# STM32_Power.net
KiCad netlist of a schematic drawn in Altium Designer
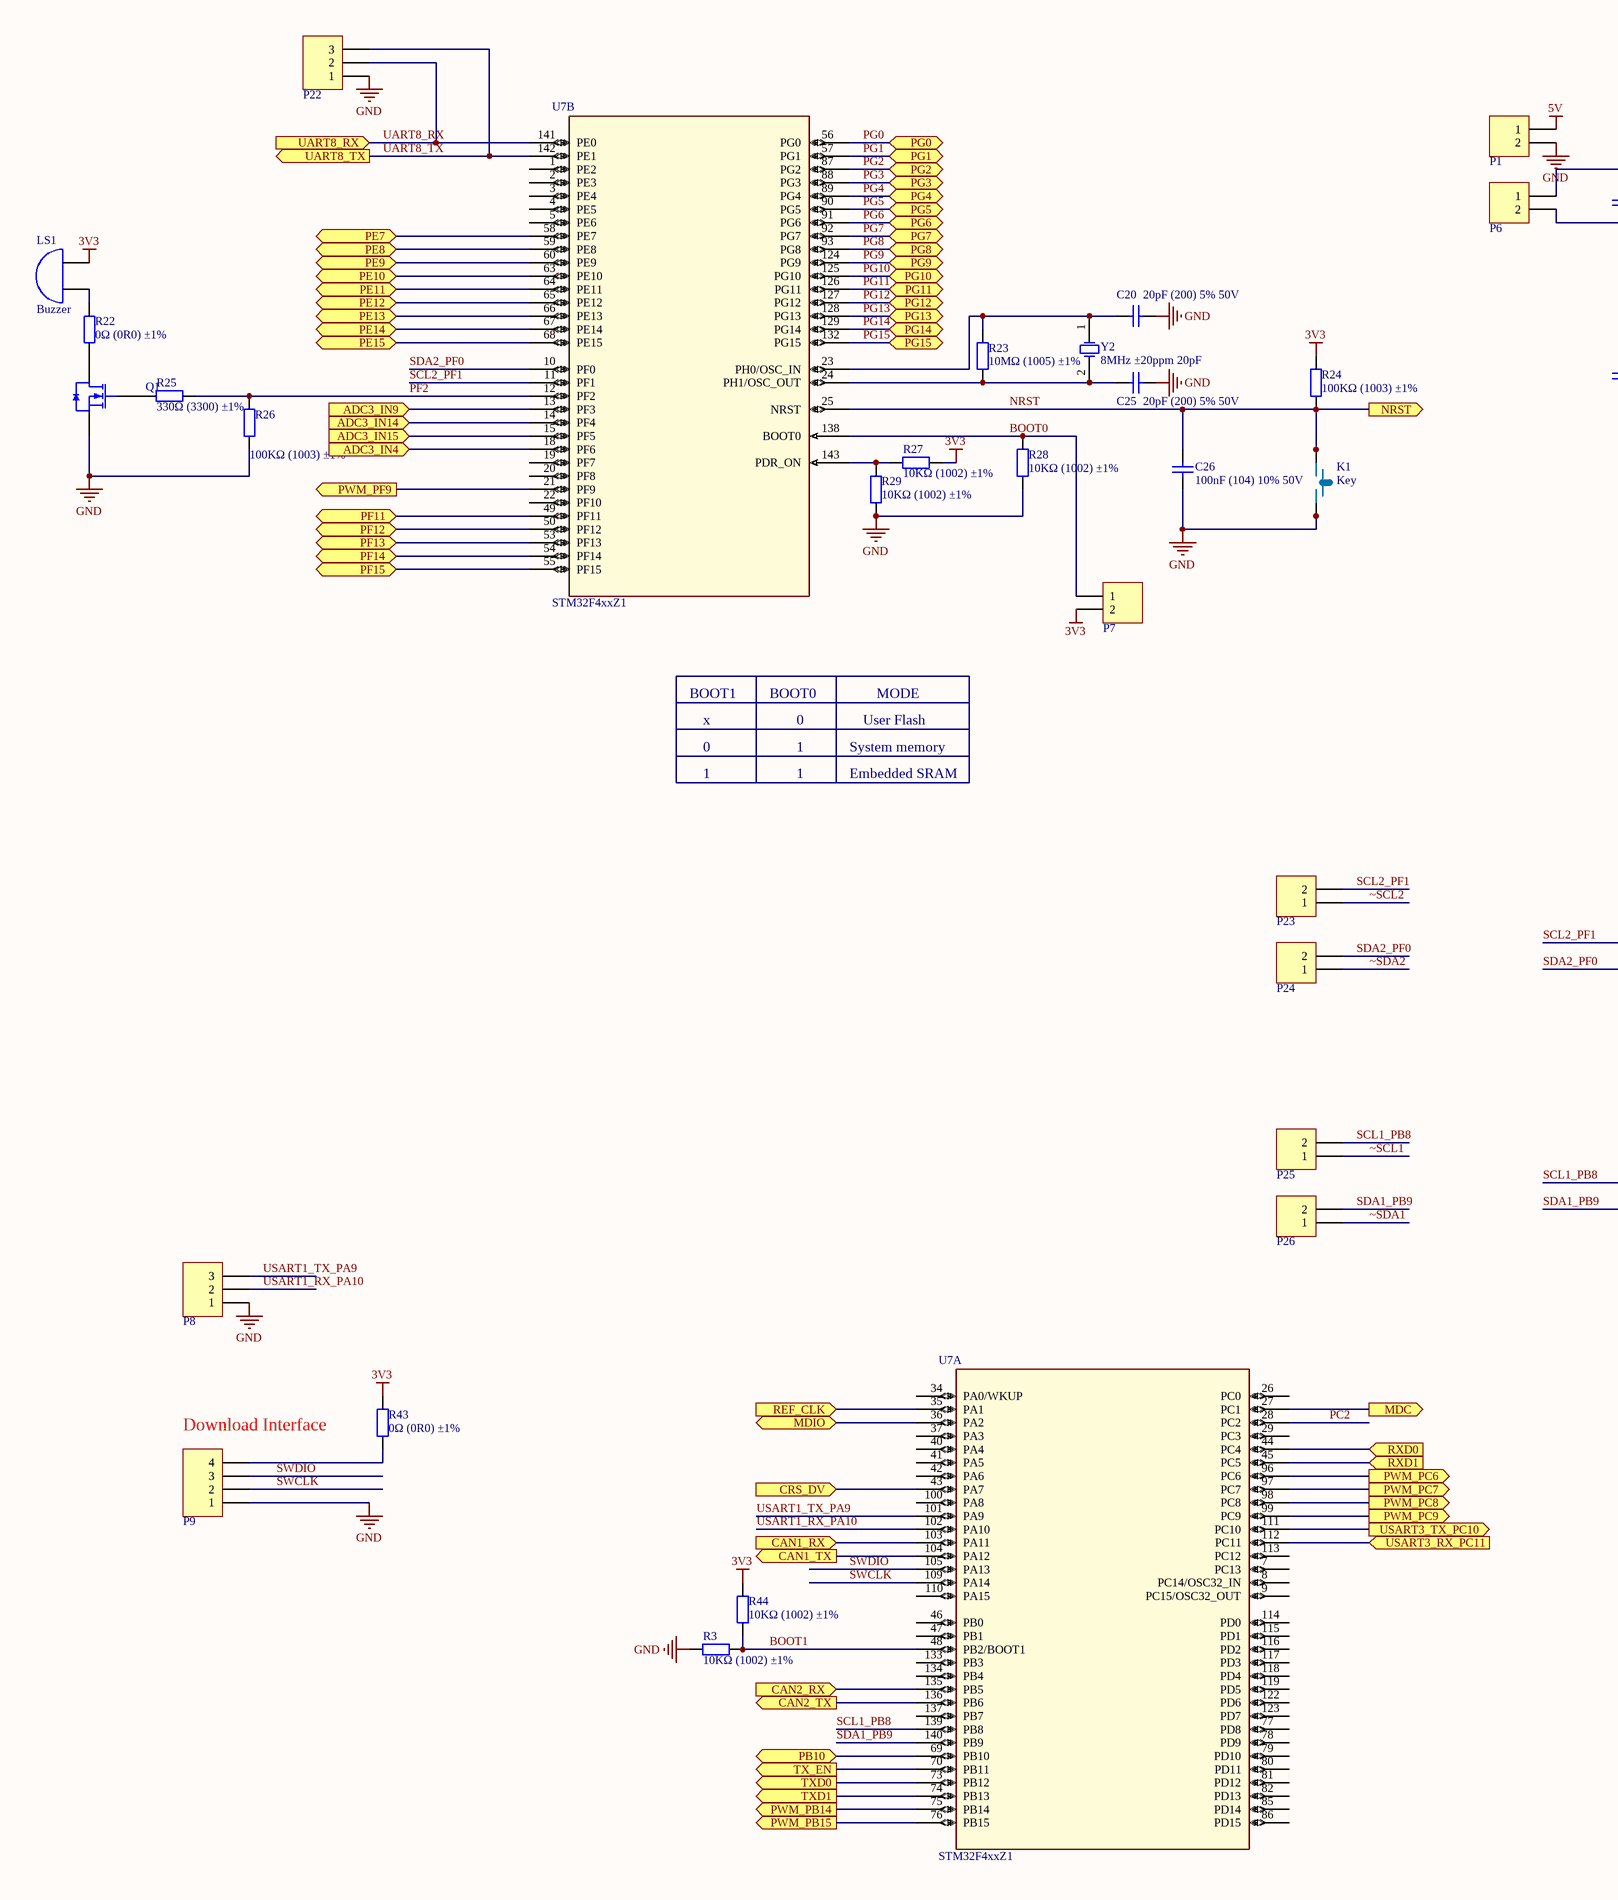
[diagram p0: STM32&Power.SchDoc, left]
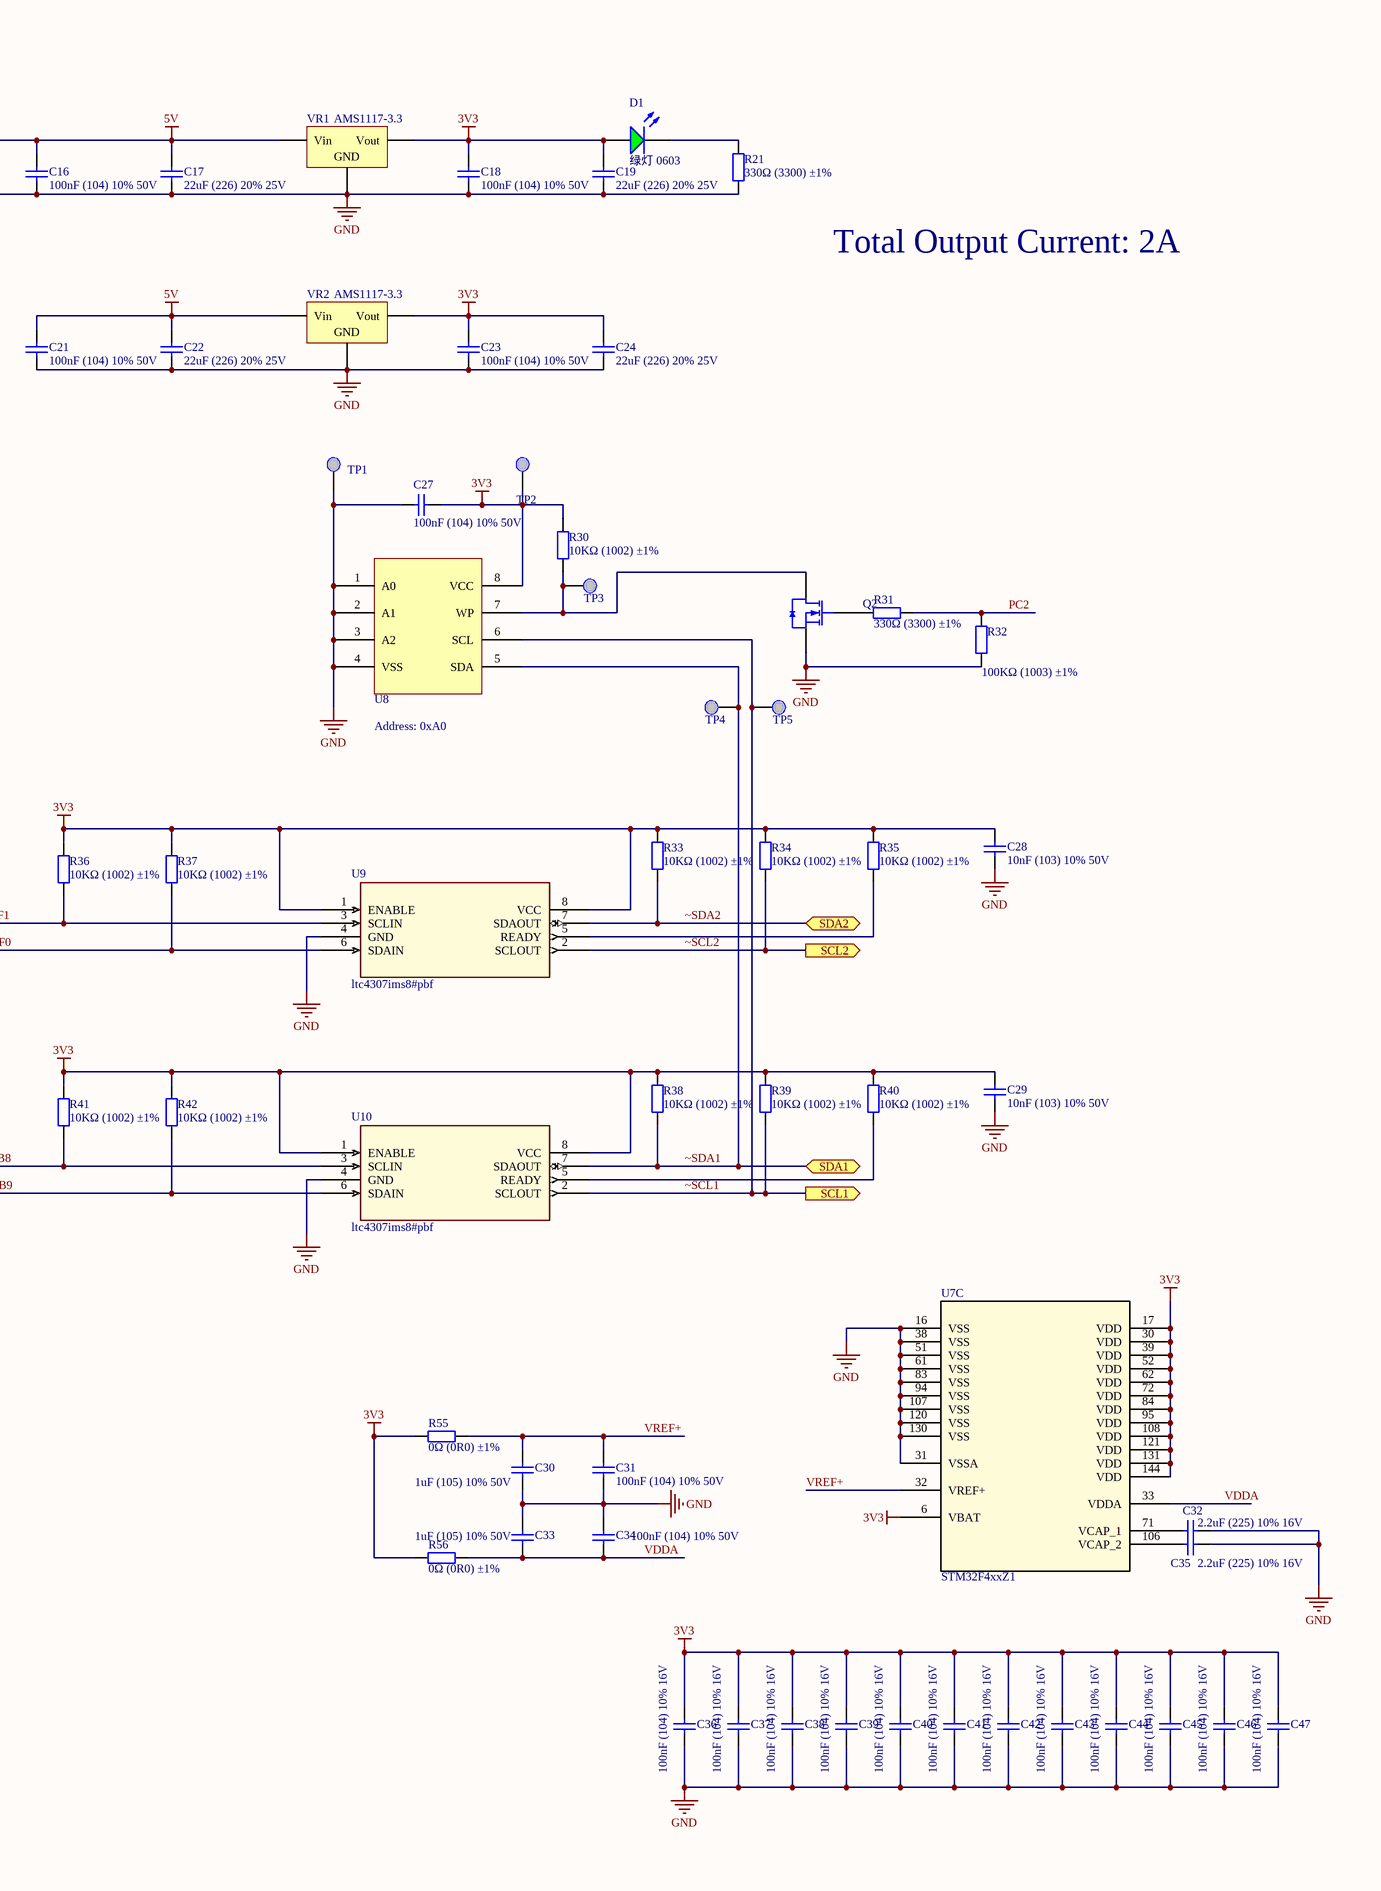
[diagram p1: STM32&Power.SchDoc, right]

(export (version "E")
  (design (tool "Eeschema 10.0.6"))
  (components
    (comp (ref "C16")
      (value "100nF (104) 10% 50V")
      (footprint "0603_C")
      (description "贴片电容")
      (libsource (lib "Miscellaneous Devices LC") (part "0603 100nF (104) 10% 50V"))
    )
    (comp (ref "C17")
      (value "22uF (226) 20% 25V")
      (footprint "0805_C")
      (description "贴片电容")
      (libsource (lib "Miscellaneous Devices LC") (part "0805 22uF (226) 20% 25V"))
    )
    (comp (ref "C18")
      (value "100nF (104) 10% 50V")
      (footprint "0603_C")
      (description "贴片电容")
      (libsource (lib "Miscellaneous Devices LC") (part "0603 100nF (104) 10% 50V"))
    )
    (comp (ref "C19")
      (value "22uF (226) 20% 25V")
      (footprint "0805_C")
      (description "贴片电容")
      (libsource (lib "Miscellaneous Devices LC") (part "0805 22uF (226) 20% 25V"))
    )
    (comp (ref "C20")
      (value "20pF (200) 5% 50V")
      (footprint "0603_C")
      (description "贴片电容")
      (libsource (lib "Miscellaneous Devices LC") (part "0603 20pF (200) 5% 50V"))
    )
    (comp (ref "C21")
      (value "100nF (104) 10% 50V")
      (footprint "0603_C")
      (description "贴片电容")
      (libsource (lib "Miscellaneous Devices LC") (part "0603 100nF (104) 10% 50V"))
    )
    (comp (ref "C22")
      (value "22uF (226) 20% 25V")
      (footprint "0805_C")
      (description "贴片电容")
      (libsource (lib "Miscellaneous Devices LC") (part "0805 22uF (226) 20% 25V"))
    )
    (comp (ref "C23")
      (value "100nF (104) 10% 50V")
      (footprint "0603_C")
      (description "贴片电容")
      (libsource (lib "Miscellaneous Devices LC") (part "0603 100nF (104) 10% 50V"))
    )
    (comp (ref "C24")
      (value "22uF (226) 20% 25V")
      (footprint "0805_C")
      (description "贴片电容")
      (libsource (lib "Miscellaneous Devices LC") (part "0805 22uF (226) 20% 25V"))
    )
    (comp (ref "C25")
      (value "20pF (200) 5% 50V")
      (footprint "0603_C")
      (description "贴片电容")
      (libsource (lib "Miscellaneous Devices LC") (part "0603 20pF (200) 5% 50V"))
    )
    (comp (ref "C26")
      (value "100nF (104) 10% 50V")
      (footprint "0603_C")
      (description "贴片电容")
      (libsource (lib "Miscellaneous Devices LC") (part "0603 100nF (104) 10% 50V"))
    )
    (comp (ref "C27")
      (value "100nF (104) 10% 50V")
      (footprint "0603_C")
      (description "贴片电容")
      (libsource (lib "Miscellaneous Devices LC") (part "0603 100nF (104) 10% 50V"))
    )
    (comp (ref "C28")
      (value "10nF (103) 10% 50V")
      (footprint "0603_C")
      (description "贴片电容")
      (libsource (lib "Miscellaneous Devices LC") (part "0603 10nF (103) 10% 50V"))
    )
    (comp (ref "C29")
      (value "10nF (103) 10% 50V")
      (footprint "0603_C")
      (description "贴片电容")
      (libsource (lib "Miscellaneous Devices LC") (part "0603 10nF (103) 10% 50V"))
    )
    (comp (ref "C30")
      (value "1uF (105) 10% 50V")
      (footprint "0603_C")
      (description "贴片电容")
      (libsource (lib "Miscellaneous Devices LC") (part "0603 1uF (105) 10% 50V"))
    )
    (comp (ref "C31")
      (value "100nF (104) 10% 50V")
      (footprint "0603_C")
      (description "贴片电容")
      (libsource (lib "Miscellaneous Devices LC") (part "0603 100nF (104) 10% 50V"))
    )
    (comp (ref "C32")
      (value "2.2uF (225) 10% 16V")
      (footprint "0603_C")
      (description "贴片电容")
      (libsource (lib "Miscellaneous Devices LC") (part "0603 2.2uF (225) 10% 16V"))
    )
    (comp (ref "C33")
      (value "1uF (105) 10% 50V")
      (footprint "0603_C")
      (description "贴片电容")
      (libsource (lib "Miscellaneous Devices LC") (part "0603 1uF (105) 10% 50V"))
    )
    (comp (ref "C34")
      (value "100nF (104) 10% 50V")
      (footprint "0603_C")
      (description "贴片电容")
      (libsource (lib "Miscellaneous Devices LC") (part "0603 100nF (104) 10% 50V"))
    )
    (comp (ref "C35")
      (value "2.2uF (225) 10% 16V")
      (footprint "0603_C")
      (description "贴片电容")
      (libsource (lib "Miscellaneous Devices LC") (part "0603 2.2uF (225) 10% 16V"))
    )
    (comp (ref "C36")
      (value "100nF (104) 10% 16V")
      (footprint "0402_C")
      (description "贴片电容")
      (libsource (lib "Miscellaneous Devices LC") (part "0402 100nF (104) 10% 16V"))
    )
    (comp (ref "C37")
      (value "100nF (104) 10% 16V")
      (footprint "0402_C")
      (description "贴片电容")
      (libsource (lib "Miscellaneous Devices LC") (part "0402 100nF (104) 10% 16V"))
    )
    (comp (ref "C38")
      (value "100nF (104) 10% 16V")
      (footprint "0402_C")
      (description "贴片电容")
      (libsource (lib "Miscellaneous Devices LC") (part "0402 100nF (104) 10% 16V"))
    )
    (comp (ref "C39")
      (value "100nF (104) 10% 16V")
      (footprint "0402_C")
      (description "贴片电容")
      (libsource (lib "Miscellaneous Devices LC") (part "0402 100nF (104) 10% 16V"))
    )
    (comp (ref "C40")
      (value "100nF (104) 10% 16V")
      (footprint "0402_C")
      (description "贴片电容")
      (libsource (lib "Miscellaneous Devices LC") (part "0402 100nF (104) 10% 16V"))
    )
    (comp (ref "C41")
      (value "100nF (104) 10% 16V")
      (footprint "0402_C")
      (description "贴片电容")
      (libsource (lib "Miscellaneous Devices LC") (part "0402 100nF (104) 10% 16V"))
    )
    (comp (ref "C42")
      (value "100nF (104) 10% 16V")
      (footprint "0402_C")
      (description "贴片电容")
      (libsource (lib "Miscellaneous Devices LC") (part "0402 100nF (104) 10% 16V"))
    )
    (comp (ref "C43")
      (value "100nF (104) 10% 16V")
      (footprint "0402_C")
      (description "贴片电容")
      (libsource (lib "Miscellaneous Devices LC") (part "0402 100nF (104) 10% 16V"))
    )
    (comp (ref "C44")
      (value "100nF (104) 10% 16V")
      (footprint "0402_C")
      (description "贴片电容")
      (libsource (lib "Miscellaneous Devices LC") (part "0402 100nF (104) 10% 16V"))
    )
    (comp (ref "C45")
      (value "100nF (104) 10% 16V")
      (footprint "0402_C")
      (description "贴片电容")
      (libsource (lib "Miscellaneous Devices LC") (part "0402 100nF (104) 10% 16V"))
    )
    (comp (ref "C46")
      (value "100nF (104) 10% 16V")
      (footprint "0402_C")
      (description "贴片电容")
      (libsource (lib "Miscellaneous Devices LC") (part "0402 100nF (104) 10% 16V"))
    )
    (comp (ref "C47")
      (value "100nF (104) 10% 16V")
      (footprint "0402_C")
      (description "贴片电容")
      (libsource (lib "Miscellaneous Devices LC") (part "0402 100nF (104) 10% 16V"))
    )
    (comp (ref "D1")
      (value "绿灯 0603")
      (footprint "0603_LED_S1")
      (description "发光二极管")
      (libsource (lib "Miscellaneous Devices LC") (part "0603 绿灯"))
    )
    (comp (ref "K1") (value "Key") (footprint "Key") (libsource (lib "MainBoard") (part "Key")))
    (comp (ref "LS1")
      (value "Buzzer")
      (footprint "buzzer")
      (description "Electrical Bell")
      (fields (field (name "PUBLISHER") "Altium Limited"))
      (libsource (lib "Miscellaneous Devices") (part "Bell"))
    )
    (comp (ref "P1")
      (value "0.1\" 2POS Header SNGL")
      (footprint "2 POS HEADER SINGLE ROW")
      (description "CONN HEADER 2POS .100\" SNGL TIN")
      (fields
        (field (name "MANUFACTURER") "Samtec Inc")
        (field (name "MANUFACTURER PART NUMBER") "TSW-150-08-T-S")
      )
      (libsource (lib "") (part "Header 2 POS_1"))
    )
    (comp (ref "P6")
      (value "B2B-PH-SM4-TB(LF)(SN)")
      (footprint "B2B-PH-SM4-TB(LF)(SN)")
      (description "CONN HEADER PH TOP 2POS 2MM SMD")
      (fields (field (name "MANUFACTURER") "JST Sales America Inc."))
      (libsource (lib "") (part "Header 2 POS_1"))
    )
    (comp (ref "P7")
      (value "0.1\" 2POS Header SNGL")
      (footprint "2 POS HEADER SINGLE ROW")
      (description "CONN HEADER 2POS .100\" SNGL TIN")
      (fields
        (field (name "MANUFACTURER") "Samtec Inc")
        (field (name "MANUFACTURER PART NUMBER") "TSW-150-08-T-S")
      )
      (libsource (lib "") (part "Header 2 POS_2"))
    )
    (comp (ref "P8")
      (value "0.1\" 3POS Header SNGL")
      (footprint "3 POS HEADER SINGLE ROW")
      (description "CONN HEADER 3POS .100\" SNGL TIN")
      (fields
        (field (name "MANUFACTURER") "Samtec Inc")
        (field (name "MANUFACTURER PART NUMBER") "TSW-150-08-T-S")
      )
      (libsource (lib "RoboteX") (part "Header 3"))
    )
    (comp (ref "P9")
      (value "0.1\" 4POS Header SNGL")
      (footprint "4 POS HEADER SINGLE ROW")
      (description "CONN HEADER 4POS .100\" SNGL TIN")
      (fields
        (field (name "MANUFACTURER") "Samtec Inc")
        (field (name "MANUFACTURER PART NUMBER") "TSW-150-08-T-S")
      )
      (libsource (lib "RoboteX") (part "Header 4"))
    )
    (comp (ref "P22")
      (value "0.1\" 3POS Header SNGL")
      (footprint "3 POS HEADER SINGLE ROW")
      (description "CONN HEADER 3POS .100\" SNGL TIN")
      (fields
        (field (name "MANUFACTURER") "Samtec Inc")
        (field (name "MANUFACTURER PART NUMBER") "TSW-150-08-T-S")
      )
      (libsource (lib "RoboteX") (part "Header 3"))
    )
    (comp (ref "P23")
      (value "0.1\" 2POS Header SNGL")
      (footprint "2 POS HEADER SINGLE ROW")
      (description "CONN HEADER 2POS .100\" SNGL TIN")
      (fields
        (field (name "MANUFACTURER") "Samtec Inc")
        (field (name "MANUFACTURER PART NUMBER") "TSW-150-08-T-S")
      )
      (libsource (lib "RoboteX") (part "Header 2 POS"))
    )
    (comp (ref "P24")
      (value "0.1\" 2POS Header SNGL")
      (footprint "2 POS HEADER SINGLE ROW")
      (description "CONN HEADER 2POS .100\" SNGL TIN")
      (fields
        (field (name "MANUFACTURER") "Samtec Inc")
        (field (name "MANUFACTURER PART NUMBER") "TSW-150-08-T-S")
      )
      (libsource (lib "RoboteX") (part "Header 2 POS"))
    )
    (comp (ref "P25")
      (value "0.1\" 2POS Header SNGL")
      (footprint "2 POS HEADER SINGLE ROW")
      (description "CONN HEADER 2POS .100\" SNGL TIN")
      (fields
        (field (name "MANUFACTURER") "Samtec Inc")
        (field (name "MANUFACTURER PART NUMBER") "TSW-150-08-T-S")
      )
      (libsource (lib "RoboteX") (part "Header 2 POS"))
    )
    (comp (ref "P26")
      (value "0.1\" 2POS Header SNGL")
      (footprint "2 POS HEADER SINGLE ROW")
      (description "CONN HEADER 2POS .100\" SNGL TIN")
      (fields
        (field (name "MANUFACTURER") "Samtec Inc")
        (field (name "MANUFACTURER PART NUMBER") "TSW-150-08-T-S")
      )
      (libsource (lib "RoboteX") (part "Header 2 POS"))
    )
    (comp (ref "Q1")
      (value "AO3400A N道沟 X0YV1T SOT-23")
      (footprint "SOT-23-3L")
      (description "MOS(场效应管)")
      (libsource (lib "Miscellaneous Devices LC") (part "AO3400A N道沟 X0YV1T SOT-23"))
    )
    (comp (ref "Q2")
      (value "AO3400A N道沟 X0YV1T SOT-23")
      (footprint "SOT-23-3L")
      (description "MOS(场效应管)")
      (libsource (lib "Miscellaneous Devices LC") (part "AO3400A N道沟 X0YV1T SOT-23"))
    )
    (comp (ref "R3")
      (value "10KΩ (1002) ±1%")
      (footprint "0603_R")
      (description "贴片电阻")
      (libsource (lib "") (part "0603 10KΩ (1002) 1%_2"))
    )
    (comp (ref "R21")
      (value "330Ω (3300) ±1%")
      (footprint "0603_R")
      (description "贴片电阻")
      (libsource (lib "Miscellaneous Devices LC") (part "0603 330Ω (3300) 1%"))
    )
    (comp (ref "R22")
      (value "0Ω (0R0) ±1%")
      (footprint "0603_R")
      (description "贴片电阻")
      (libsource (lib "") (part "0603 0Ω (0R0) 1%_1"))
    )
    (comp (ref "R23")
      (value "10MΩ (1005) ±1%")
      (footprint "0603_R")
      (description "贴片电阻")
      (libsource (lib "Miscellaneous Devices LC") (part "0603 10MΩ (1005) 1%"))
    )
    (comp (ref "R24")
      (value "100KΩ (1003) ±1%")
      (footprint "0603_R")
      (description "贴片电阻")
      (libsource (lib "Miscellaneous Devices LC") (part "0603 100KΩ (1003) 1%"))
    )
    (comp (ref "R25")
      (value "330Ω (3300) ±1%")
      (footprint "0603_R")
      (description "贴片电阻")
      (libsource (lib "") (part "0603 330Ω (3300) 1%_1"))
    )
    (comp (ref "R26")
      (value "100KΩ (1003) ±1%")
      (footprint "0603_R")
      (description "贴片电阻")
      (libsource (lib "Miscellaneous Devices LC") (part "0603 100KΩ (1003) 1%"))
    )
    (comp (ref "R27")
      (value "10KΩ (1002) ±1%")
      (footprint "0603_R")
      (description "贴片电阻")
      (libsource (lib "") (part "0603 10KΩ (1002) 1%_1"))
    )
    (comp (ref "R28")
      (value "10KΩ (1002) ±1%")
      (footprint "0603_R")
      (description "贴片电阻")
      (libsource (lib "Miscellaneous Devices LC") (part "0603 10KΩ (1002) 1%"))
    )
    (comp (ref "R29")
      (value "10KΩ (1002) ±1%")
      (footprint "0603_R")
      (description "贴片电阻")
      (libsource (lib "Miscellaneous Devices LC") (part "0603 10KΩ (1002) 1%"))
    )
    (comp (ref "R30")
      (value "10KΩ (1002) ±1%")
      (footprint "0603_R")
      (description "贴片电阻")
      (libsource (lib "Miscellaneous Devices LC") (part "0603 10KΩ (1002) 1%"))
    )
    (comp (ref "R31")
      (value "330Ω (3300) ±1%")
      (footprint "0603_R")
      (description "贴片电阻")
      (libsource (lib "") (part "0603 330Ω (3300) 1%_1"))
    )
    (comp (ref "R32")
      (value "100KΩ (1003) ±1%")
      (footprint "0603_R")
      (description "贴片电阻")
      (libsource (lib "Miscellaneous Devices LC") (part "0603 100KΩ (1003) 1%"))
    )
    (comp (ref "R33")
      (value "10KΩ (1002) ±1%")
      (footprint "0603_R")
      (description "贴片电阻")
      (libsource (lib "Miscellaneous Devices LC") (part "0603 10KΩ (1002) 1%"))
    )
    (comp (ref "R34")
      (value "10KΩ (1002) ±1%")
      (footprint "0603_R")
      (description "贴片电阻")
      (libsource (lib "Miscellaneous Devices LC") (part "0603 10KΩ (1002) 1%"))
    )
    (comp (ref "R35")
      (value "10KΩ (1002) ±1%")
      (footprint "0603_R")
      (description "贴片电阻")
      (libsource (lib "Miscellaneous Devices LC") (part "0603 10KΩ (1002) 1%"))
    )
    (comp (ref "R36")
      (value "10KΩ (1002) ±1%")
      (footprint "0603_R")
      (description "贴片电阻")
      (libsource (lib "Miscellaneous Devices LC") (part "0603 10KΩ (1002) 1%"))
    )
    (comp (ref "R37")
      (value "10KΩ (1002) ±1%")
      (footprint "0603_R")
      (description "贴片电阻")
      (libsource (lib "Miscellaneous Devices LC") (part "0603 10KΩ (1002) 1%"))
    )
    (comp (ref "R38")
      (value "10KΩ (1002) ±1%")
      (footprint "0603_R")
      (description "贴片电阻")
      (libsource (lib "Miscellaneous Devices LC") (part "0603 10KΩ (1002) 1%"))
    )
    (comp (ref "R39")
      (value "10KΩ (1002) ±1%")
      (footprint "0603_R")
      (description "贴片电阻")
      (libsource (lib "Miscellaneous Devices LC") (part "0603 10KΩ (1002) 1%"))
    )
    (comp (ref "R40")
      (value "10KΩ (1002) ±1%")
      (footprint "0603_R")
      (description "贴片电阻")
      (libsource (lib "Miscellaneous Devices LC") (part "0603 10KΩ (1002) 1%"))
    )
    (comp (ref "R41")
      (value "10KΩ (1002) ±1%")
      (footprint "0603_R")
      (description "贴片电阻")
      (libsource (lib "Miscellaneous Devices LC") (part "0603 10KΩ (1002) 1%"))
    )
    (comp (ref "R42")
      (value "10KΩ (1002) ±1%")
      (footprint "0603_R")
      (description "贴片电阻")
      (libsource (lib "Miscellaneous Devices LC") (part "0603 10KΩ (1002) 1%"))
    )
    (comp (ref "R43")
      (value "0Ω (0R0) ±1%")
      (footprint "0603_R")
      (description "贴片电阻")
      (libsource (lib "") (part "0603 0Ω (0R0) 1%_1"))
    )
    (comp (ref "R44")
      (value "10KΩ (1002) ±1%")
      (footprint "0603_R")
      (description "贴片电阻")
      (libsource (lib "Miscellaneous Devices LC") (part "0603 10KΩ (1002) 1%"))
    )
    (comp (ref "R55")
      (value "0Ω (0R0) ±1%")
      (footprint "0603_R")
      (description "贴片电阻")
      (libsource (lib "Miscellaneous Devices LC") (part "0603 0Ω (0R0) 1%"))
    )
    (comp (ref "R56")
      (value "0Ω (0R0) ±1%")
      (footprint "0603_R")
      (description "贴片电阻")
      (libsource (lib "Miscellaneous Devices LC") (part "0603 0Ω (0R0) 1%"))
    )
    (comp (ref "TP1")
      (value "Test Point, 60mil")
      (footprint "test_point_60_mil")
      (libsource (lib "RoboteX") (part "test_point"))
    )
    (comp (ref "TP2")
      (value "Test Point, 60mil")
      (footprint "test_point_60_mil")
      (libsource (lib "RoboteX") (part "test_point"))
    )
    (comp (ref "TP3")
      (value "Test Point, 60mil")
      (footprint "test_point_60_mil")
      (libsource (lib "RoboteX") (part "test_point"))
    )
    (comp (ref "TP4")
      (value "Test Point, 60mil")
      (footprint "test_point_60_mil")
      (libsource (lib "RoboteX") (part "test_point"))
    )
    (comp (ref "TP5")
      (value "Test Point, 60mil")
      (footprint "test_point_60_mil")
      (libsource (lib "RoboteX") (part "test_point"))
    )
    (comp (ref "U7")
      (value "STM32F4xxZ1")
      (footprint "LQFP-144_20x20x05P")
      (description "Imported")
      (fields
        (field (name "MANUFACTURER_PART_NUMBER") "stm32f4xxz1")
        (field (name "COPYRIGHT") "Copyright (C) 2016 Accelerated Designs. All rights reserved")
      )
      (libsource (lib "2018-10-14_16-01-17") (part "STM32F4xxZ1"))
    )
    (comp (ref "U8")
      (value "M24C02-WMN6TP")
      (footprint "SOIC127P600-8CM")
      (description "IC EEPROM 2KBIT 400KHZ 8SOIC")
      (fields (field (name "MANUFACTURER") "STMicroelectronics"))
      (libsource (lib "RoboteX") (part "24LC01B-I/SN"))
    )
    (comp (ref "U9")
      (value "ltc4307ims8#pbf")
      (footprint "MSOP-8_MS")
      (description "Imported")
      (libsource (lib "lib") (part "ltc4307ims8#pbf"))
    )
    (comp (ref "U10")
      (value "ltc4307ims8#pbf")
      (footprint "MSOP-8_MS")
      (description "Imported")
      (libsource (lib "lib") (part "ltc4307ims8#pbf"))
    )
    (comp (ref "VR1")
      (value "AMS1117-3.3")
      (footprint "SOT-223")
      (description "低压差线性稳压(LDO)")
      (libsource (lib "Miscellaneous Devices LC") (part "SOT-223 AMS1117-3.3"))
    )
    (comp (ref "VR2")
      (value "AMS1117-3.3")
      (footprint "SOT-223")
      (description "低压差线性稳压(LDO)")
      (libsource (lib "Miscellaneous Devices LC") (part "SOT-223 AMS1117-3.3"))
    )
    (comp (ref "Y2")
      (value "8MHz ±20ppm 20pF")
      (footprint "SMD-5032_2P")
      (description "贴片晶振")
      (libsource (lib "Miscellaneous Devices LC") (part "SMD-5032_2P 8MHz 20ppm 20pF"))
    )
  )
  (nets
    (net (code "1") (name "/ADC3_IN4") (class "Default")
      (node (ref "U7") (pin "18") (pinfunction "PF6_18") (pintype "bidirectional"))
    )
    (net (code "2") (name "/ADC3_IN9") (class "Default")
      (node (ref "U7") (pin "13") (pinfunction "PF3_13") (pintype "bidirectional"))
    )
    (net (code "3") (name "/ADC3_IN14") (class "Default")
      (node (ref "U7") (pin "14") (pinfunction "PF4_14") (pintype "bidirectional"))
    )
    (net (code "4") (name "/ADC3_IN15") (class "Default")
      (node (ref "U7") (pin "15") (pinfunction "PF5_15") (pintype "bidirectional"))
    )
    (net (code "5") (name "/BOOT0") (class "Default")
      (node (ref "P7") (pin "1") (pinfunction "1_1") (pintype "passive"))
      (node (ref "R28") (pin "2") (pinfunction "2_2") (pintype "passive"))
      (node (ref "U7") (pin "138") (pinfunction "BOOT0_138") (pintype "input"))
    )
    (net (code "6") (name "/BOOT1") (class "Default")
      (node (ref "R3") (pin "1") (pinfunction "1_1") (pintype "passive"))
      (node (ref "R44") (pin "1") (pinfunction "1_1") (pintype "passive"))
      (node (ref "U7") (pin "48") (pinfunction "PB2/BOOT1_48") (pintype "bidirectional"))
    )
    (net (code "7") (name "/CAN1_RX") (class "Default")
      (node (ref "U7") (pin "103") (pinfunction "PA11_103") (pintype "bidirectional"))
    )
    (net (code "8") (name "/CAN1_TX") (class "Default")
      (node (ref "U7") (pin "104") (pinfunction "PA12_104") (pintype "bidirectional"))
    )
    (net (code "9") (name "/CAN2_RX") (class "Default")
      (node (ref "U7") (pin "135") (pinfunction "PB5_135") (pintype "bidirectional"))
    )
    (net (code "10") (name "/CAN2_TX") (class "Default")
      (node (ref "U7") (pin "136") (pinfunction "PB6_136") (pintype "bidirectional"))
    )
    (net (code "11") (name "/CRS_DV") (class "Default")
      (node (ref "U7") (pin "43") (pinfunction "PA7_43") (pintype "bidirectional"))
    )
    (net (code "12") (name "/MDC") (class "Default")
      (node (ref "U7") (pin "27") (pinfunction "PC1_27") (pintype "bidirectional"))
    )
    (net (code "13") (name "/MDIO") (class "Default")
      (node (ref "U7") (pin "36") (pinfunction "PA2_36") (pintype "bidirectional"))
    )
    (net (code "14") (name "/NRST") (class "Default")
      (node (ref "C26") (pin "2") (pinfunction "2_2") (pintype "passive"))
      (node (ref "K1") (pin "1") (pinfunction "1_1") (pintype "passive"))
      (node (ref "K1") (pin "2") (pinfunction "2_2") (pintype "passive"))
      (node (ref "R24") (pin "1") (pinfunction "1_1") (pintype "passive"))
      (node (ref "U7") (pin "25") (pinfunction "NRST_25") (pintype "bidirectional"))
    )
    (net (code "15") (name "/PB10") (class "Default")
      (node (ref "U7") (pin "69") (pinfunction "PB10_69") (pintype "bidirectional"))
    )
    (net (code "16") (name "/PC2") (class "Default")
      (node (ref "R31") (pin "2") (pinfunction "2_2") (pintype "passive"))
      (node (ref "R32") (pin "2") (pinfunction "2_2") (pintype "passive"))
      (node (ref "U7") (pin "28") (pinfunction "PC2_28") (pintype "bidirectional"))
    )
    (net (code "17") (name "/PE7") (class "Default")
      (node (ref "U7") (pin "58") (pinfunction "PE7_58") (pintype "bidirectional"))
    )
    (net (code "18") (name "/PE8") (class "Default")
      (node (ref "U7") (pin "59") (pinfunction "PE8_59") (pintype "bidirectional"))
    )
    (net (code "19") (name "/PE9") (class "Default")
      (node (ref "U7") (pin "60") (pinfunction "PE9_60") (pintype "bidirectional"))
    )
    (net (code "20") (name "/PE10") (class "Default")
      (node (ref "U7") (pin "63") (pinfunction "PE10_63") (pintype "bidirectional"))
    )
    (net (code "21") (name "/PE11") (class "Default")
      (node (ref "U7") (pin "64") (pinfunction "PE11_64") (pintype "bidirectional"))
    )
    (net (code "22") (name "/PE12") (class "Default")
      (node (ref "U7") (pin "65") (pinfunction "PE12_65") (pintype "bidirectional"))
    )
    (net (code "23") (name "/PE13") (class "Default")
      (node (ref "U7") (pin "66") (pinfunction "PE13_66") (pintype "bidirectional"))
    )
    (net (code "24") (name "/PE14") (class "Default")
      (node (ref "U7") (pin "67") (pinfunction "PE14_67") (pintype "bidirectional"))
    )
    (net (code "25") (name "/PE15") (class "Default")
      (node (ref "U7") (pin "68") (pinfunction "PE15_68") (pintype "bidirectional"))
    )
    (net (code "26") (name "/PF2") (class "Default")
      (node (ref "R25") (pin "2") (pinfunction "2_2") (pintype "passive"))
      (node (ref "R26") (pin "2") (pinfunction "2_2") (pintype "passive"))
      (node (ref "U7") (pin "12") (pinfunction "PF2_12") (pintype "bidirectional"))
    )
    (net (code "27") (name "/PF11") (class "Default")
      (node (ref "U7") (pin "49") (pinfunction "PF11_49") (pintype "bidirectional"))
    )
    (net (code "28") (name "/PF12") (class "Default")
      (node (ref "U7") (pin "50") (pinfunction "PF12_50") (pintype "bidirectional"))
    )
    (net (code "29") (name "/PF13") (class "Default")
      (node (ref "U7") (pin "53") (pinfunction "PF13_53") (pintype "bidirectional"))
    )
    (net (code "30") (name "/PF14") (class "Default")
      (node (ref "U7") (pin "54") (pinfunction "PF14_54") (pintype "bidirectional"))
    )
    (net (code "31") (name "/PF15") (class "Default")
      (node (ref "U7") (pin "55") (pinfunction "PF15_55") (pintype "bidirectional"))
    )
    (net (code "32") (name "/PG0") (class "Default")
      (node (ref "U7") (pin "56") (pinfunction "PG0_56") (pintype "bidirectional"))
    )
    (net (code "33") (name "/PG1") (class "Default")
      (node (ref "U7") (pin "57") (pinfunction "PG1_57") (pintype "bidirectional"))
    )
    (net (code "34") (name "/PG2") (class "Default")
      (node (ref "U7") (pin "87") (pinfunction "PG2_87") (pintype "bidirectional"))
    )
    (net (code "35") (name "/PG3") (class "Default")
      (node (ref "U7") (pin "88") (pinfunction "PG3_88") (pintype "bidirectional"))
    )
    (net (code "36") (name "/PG4") (class "Default")
      (node (ref "U7") (pin "89") (pinfunction "PG4_89") (pintype "bidirectional"))
    )
    (net (code "37") (name "/PG5") (class "Default")
      (node (ref "U7") (pin "90") (pinfunction "PG5_90") (pintype "bidirectional"))
    )
    (net (code "38") (name "/PG6") (class "Default")
      (node (ref "U7") (pin "91") (pinfunction "PG6_91") (pintype "bidirectional"))
    )
    (net (code "39") (name "/PG7") (class "Default")
      (node (ref "U7") (pin "92") (pinfunction "PG7_92") (pintype "bidirectional"))
    )
    (net (code "40") (name "/PG8") (class "Default")
      (node (ref "U7") (pin "93") (pinfunction "PG8_93") (pintype "bidirectional"))
    )
    (net (code "41") (name "/PG9") (class "Default")
      (node (ref "U7") (pin "124") (pinfunction "PG9_124") (pintype "bidirectional"))
    )
    (net (code "42") (name "/PG10") (class "Default")
      (node (ref "U7") (pin "125") (pinfunction "PG10_125") (pintype "bidirectional"))
    )
    (net (code "43") (name "/PG11") (class "Default")
      (node (ref "U7") (pin "126") (pinfunction "PG11_126") (pintype "bidirectional"))
    )
    (net (code "44") (name "/PG12") (class "Default")
      (node (ref "U7") (pin "127") (pinfunction "PG12_127") (pintype "bidirectional"))
    )
    (net (code "45") (name "/PG13") (class "Default")
      (node (ref "U7") (pin "128") (pinfunction "PG13_128") (pintype "bidirectional"))
    )
    (net (code "46") (name "/PG14") (class "Default")
      (node (ref "U7") (pin "129") (pinfunction "PG14_129") (pintype "bidirectional"))
    )
    (net (code "47") (name "/PG15") (class "Default")
      (node (ref "U7") (pin "132") (pinfunction "PG15_132") (pintype "bidirectional"))
    )
    (net (code "48") (name "/PWM_PB14") (class "Default")
      (node (ref "U7") (pin "75") (pinfunction "PB14_75") (pintype "bidirectional"))
    )
    (net (code "49") (name "/PWM_PB15") (class "Default")
      (node (ref "U7") (pin "76") (pinfunction "PB15_76") (pintype "bidirectional"))
    )
    (net (code "50") (name "/PWM_PC6") (class "Default")
      (node (ref "U7") (pin "96") (pinfunction "PC6_96") (pintype "bidirectional"))
    )
    (net (code "51") (name "/PWM_PC7") (class "Default")
      (node (ref "U7") (pin "97") (pinfunction "PC7_97") (pintype "bidirectional"))
    )
    (net (code "52") (name "/PWM_PC8") (class "Default")
      (node (ref "U7") (pin "98") (pinfunction "PC8_98") (pintype "bidirectional"))
    )
    (net (code "53") (name "/PWM_PC9") (class "Default")
      (node (ref "U7") (pin "99") (pinfunction "PC9_99") (pintype "bidirectional"))
    )
    (net (code "54") (name "/PWM_PF9") (class "Default")
      (node (ref "U7") (pin "21") (pinfunction "PF9_21") (pintype "bidirectional"))
    )
    (net (code "55") (name "/REF_CLK") (class "Default")
      (node (ref "U7") (pin "35") (pinfunction "PA1_35") (pintype "bidirectional"))
    )
    (net (code "56") (name "/RXD0") (class "Default")
      (node (ref "U7") (pin "44") (pinfunction "PC4_44") (pintype "bidirectional"))
    )
    (net (code "57") (name "/RXD1") (class "Default")
      (node (ref "U7") (pin "45") (pinfunction "PC5_45") (pintype "bidirectional"))
    )
    (net (code "58") (name "/SCL1_PB8") (class "Default")
      (node (ref "P25") (pin "2") (pinfunction "2_2") (pintype "passive"))
      (node (ref "R41") (pin "1") (pinfunction "1_1") (pintype "passive"))
      (node (ref "U10") (pin "3") (pinfunction "SCLIN_3") (pintype "input"))
      (node (ref "U7") (pin "139") (pinfunction "PB8_139") (pintype "bidirectional"))
    )
    (net (code "59") (name "/SCL2_PF1") (class "Default")
      (node (ref "P23") (pin "2") (pinfunction "2_2") (pintype "passive"))
      (node (ref "R36") (pin "1") (pinfunction "1_1") (pintype "passive"))
      (node (ref "U7") (pin "11") (pinfunction "PF1_11") (pintype "bidirectional"))
      (node (ref "U9") (pin "3") (pinfunction "SCLIN_3") (pintype "input"))
    )
    (net (code "60") (name "/SDA1_PB9") (class "Default")
      (node (ref "P26") (pin "2") (pinfunction "2_2") (pintype "passive"))
      (node (ref "R42") (pin "1") (pinfunction "1_1") (pintype "passive"))
      (node (ref "U10") (pin "6") (pinfunction "SDAIN_6") (pintype "input"))
      (node (ref "U7") (pin "140") (pinfunction "PB9_140") (pintype "bidirectional"))
    )
    (net (code "61") (name "/SDA2_PF0") (class "Default")
      (node (ref "P24") (pin "2") (pinfunction "2_2") (pintype "passive"))
      (node (ref "R37") (pin "1") (pinfunction "1_1") (pintype "passive"))
      (node (ref "U7") (pin "10") (pinfunction "PF0_10") (pintype "bidirectional"))
      (node (ref "U9") (pin "6") (pinfunction "SDAIN_6") (pintype "input"))
    )
    (net (code "62") (name "/SWCLK") (class "Default")
      (node (ref "P9") (pin "2") (pinfunction "2_2") (pintype "passive"))
      (node (ref "U7") (pin "109") (pinfunction "PA14_109") (pintype "bidirectional"))
    )
    (net (code "63") (name "/SWDIO") (class "Default")
      (node (ref "P9") (pin "3") (pinfunction "3_3") (pintype "passive"))
      (node (ref "U7") (pin "105") (pinfunction "PA13_105") (pintype "bidirectional"))
    )
    (net (code "64") (name "/TXD0") (class "Default")
      (node (ref "U7") (pin "73") (pinfunction "PB12_73") (pintype "bidirectional"))
    )
    (net (code "65") (name "/TXD1") (class "Default")
      (node (ref "U7") (pin "74") (pinfunction "PB13_74") (pintype "bidirectional"))
    )
    (net (code "66") (name "/TX_EN") (class "Default")
      (node (ref "U7") (pin "70") (pinfunction "PB11_70") (pintype "bidirectional"))
    )
    (net (code "67") (name "/UART8_RX") (class "Default")
      (node (ref "P22") (pin "2") (pinfunction "2_2") (pintype "passive"))
      (node (ref "U7") (pin "141") (pinfunction "PE0_141") (pintype "bidirectional"))
    )
    (net (code "68") (name "/UART8_TX") (class "Default")
      (node (ref "P22") (pin "3") (pinfunction "3_3") (pintype "passive"))
      (node (ref "U7") (pin "142") (pinfunction "PE1_142") (pintype "bidirectional"))
    )
    (net (code "69") (name "/USART1_RX_PA10") (class "Default")
      (node (ref "P8") (pin "2") (pinfunction "2_2") (pintype "passive"))
      (node (ref "U7") (pin "102") (pinfunction "PA10_102") (pintype "bidirectional"))
    )
    (net (code "70") (name "/USART1_TX_PA9") (class "Default")
      (node (ref "P8") (pin "3") (pinfunction "3_3") (pintype "passive"))
      (node (ref "U7") (pin "101") (pinfunction "PA9_101") (pintype "bidirectional"))
    )
    (net (code "71") (name "/USART3_RX_PC11") (class "Default")
      (node (ref "U7") (pin "112") (pinfunction "PC11_112") (pintype "bidirectional"))
    )
    (net (code "72") (name "/USART3_TX_PC10") (class "Default")
      (node (ref "U7") (pin "111") (pinfunction "PC10_111") (pintype "bidirectional"))
    )
    (net (code "73") (name "/VDDA") (class "Default")
      (node (ref "C33") (pin "2") (pinfunction "2_2") (pintype "passive"))
      (node (ref "C34") (pin "1") (pinfunction "1_1") (pintype "passive"))
      (node (ref "R56") (pin "2") (pinfunction "2_2") (pintype "passive"))
      (node (ref "U7") (pin "33") (pinfunction "VDDA_33") (pintype "power_in"))
    )
    (net (code "74") (name "/VREF+") (class "Default")
      (node (ref "C30") (pin "1") (pinfunction "1_1") (pintype "passive"))
      (node (ref "C31") (pin "2") (pinfunction "2_2") (pintype "passive"))
      (node (ref "R55") (pin "2") (pinfunction "2_2") (pintype "passive"))
      (node (ref "U7") (pin "32") (pinfunction "VREF+_32") (pintype "power_in"))
    )
    (net (code "75") (name "/~SCL1") (class "Default")
      (node (ref "P25") (pin "1") (pinfunction "1_1") (pintype "passive"))
      (node (ref "R39") (pin "1") (pinfunction "1_1") (pintype "passive"))
      (node (ref "TP5") (pin "0") (pinfunction "0_0") (pintype "passive"))
      (node (ref "U10") (pin "2") (pinfunction "SCLOUT_2") (pintype "output"))
      (node (ref "U8") (pin "6") (pinfunction "SCL_6") (pintype "passive"))
    )
    (net (code "76") (name "/~SCL2") (class "Default")
      (node (ref "P23") (pin "1") (pinfunction "1_1") (pintype "passive"))
      (node (ref "R34") (pin "1") (pinfunction "1_1") (pintype "passive"))
      (node (ref "U9") (pin "2") (pinfunction "SCLOUT_2") (pintype "output"))
    )
    (net (code "77") (name "/~SDA1") (class "Default")
      (node (ref "P26") (pin "1") (pinfunction "1_1") (pintype "passive"))
      (node (ref "R38") (pin "1") (pinfunction "1_1") (pintype "passive"))
      (node (ref "TP4") (pin "0") (pinfunction "0_0") (pintype "passive"))
      (node (ref "U10") (pin "7") (pinfunction "SDAOUT_7") (pintype "bidirectional"))
      (node (ref "U8") (pin "5") (pinfunction "SDA_5") (pintype "passive"))
    )
    (net (code "78") (name "/~SDA2") (class "Default")
      (node (ref "P24") (pin "1") (pinfunction "1_1") (pintype "passive"))
      (node (ref "R33") (pin "1") (pinfunction "1_1") (pintype "passive"))
      (node (ref "U9") (pin "7") (pinfunction "SDAOUT_7") (pintype "bidirectional"))
    )
    (net (code "79") (name "3V3") (class "Default")
      (node (ref "C18") (pin "2") (pinfunction "2_2") (pintype "passive"))
      (node (ref "C19") (pin "2") (pinfunction "2_2") (pintype "passive"))
      (node (ref "C23") (pin "2") (pinfunction "2_2") (pintype "passive"))
      (node (ref "C24") (pin "2") (pinfunction "2_2") (pintype "passive"))
      (node (ref "C27") (pin "1") (pinfunction "1_1") (pintype "passive"))
      (node (ref "C28") (pin "2") (pinfunction "2_2") (pintype "passive"))
      (node (ref "C29") (pin "2") (pinfunction "2_2") (pintype "passive"))
      (node (ref "C36") (pin "2") (pinfunction "2_2") (pintype "passive"))
      (node (ref "C37") (pin "2") (pinfunction "2_2") (pintype "passive"))
      (node (ref "C38") (pin "2") (pinfunction "2_2") (pintype "passive"))
      (node (ref "C39") (pin "2") (pinfunction "2_2") (pintype "passive"))
      (node (ref "C40") (pin "2") (pinfunction "2_2") (pintype "passive"))
      (node (ref "C41") (pin "2") (pinfunction "2_2") (pintype "passive"))
      (node (ref "C42") (pin "2") (pinfunction "2_2") (pintype "passive"))
      (node (ref "C43") (pin "2") (pinfunction "2_2") (pintype "passive"))
      (node (ref "C44") (pin "2") (pinfunction "2_2") (pintype "passive"))
      (node (ref "C45") (pin "2") (pinfunction "2_2") (pintype "passive"))
      (node (ref "C46") (pin "2") (pinfunction "2_2") (pintype "passive"))
      (node (ref "C47") (pin "2") (pinfunction "2_2") (pintype "passive"))
      (node (ref "D1") (pin "A") (pinfunction "A_A") (pintype "passive"))
      (node (ref "LS1") (pin "1") (pinfunction "A_1") (pintype "passive"))
      (node (ref "P7") (pin "2") (pinfunction "2_2") (pintype "passive"))
      (node (ref "R24") (pin "2") (pinfunction "2_2") (pintype "passive"))
      (node (ref "R27") (pin "2") (pinfunction "2_2") (pintype "passive"))
      (node (ref "R30") (pin "2") (pinfunction "2_2") (pintype "passive"))
      (node (ref "R33") (pin "2") (pinfunction "2_2") (pintype "passive"))
      (node (ref "R34") (pin "2") (pinfunction "2_2") (pintype "passive"))
      (node (ref "R35") (pin "2") (pinfunction "2_2") (pintype "passive"))
      (node (ref "R36") (pin "2") (pinfunction "2_2") (pintype "passive"))
      (node (ref "R37") (pin "2") (pinfunction "2_2") (pintype "passive"))
      (node (ref "R38") (pin "2") (pinfunction "2_2") (pintype "passive"))
      (node (ref "R39") (pin "2") (pinfunction "2_2") (pintype "passive"))
      (node (ref "R40") (pin "2") (pinfunction "2_2") (pintype "passive"))
      (node (ref "R41") (pin "2") (pinfunction "2_2") (pintype "passive"))
      (node (ref "R42") (pin "2") (pinfunction "2_2") (pintype "passive"))
      (node (ref "R43") (pin "2") (pinfunction "2_2") (pintype "passive"))
      (node (ref "R44") (pin "2") (pinfunction "2_2") (pintype "passive"))
      (node (ref "R55") (pin "1") (pinfunction "1_1") (pintype "passive"))
      (node (ref "R56") (pin "1") (pinfunction "1_1") (pintype "passive"))
      (node (ref "TP2") (pin "0") (pinfunction "0_0") (pintype "passive"))
      (node (ref "U10") (pin "1") (pinfunction "ENABLE_1") (pintype "input"))
      (node (ref "U10") (pin "8") (pinfunction "VCC_8") (pintype "power_in"))
      (node (ref "U7") (pin "108") (pinfunction "VDD_108") (pintype "power_in"))
      (node (ref "U7") (pin "121") (pinfunction "VDD_121") (pintype "power_in"))
      (node (ref "U7") (pin "131") (pinfunction "VDD_131") (pintype "power_in"))
      (node (ref "U7") (pin "144") (pinfunction "VDD_144") (pintype "power_in"))
      (node (ref "U7") (pin "17") (pinfunction "VDD_17") (pintype "power_in"))
      (node (ref "U7") (pin "30") (pinfunction "VDD_30") (pintype "power_in"))
      (node (ref "U7") (pin "39") (pinfunction "VDD_39") (pintype "power_in"))
      (node (ref "U7") (pin "52") (pinfunction "VDD_52") (pintype "power_in"))
      (node (ref "U7") (pin "6") (pinfunction "VBAT_6") (pintype "power_in"))
      (node (ref "U7") (pin "62") (pinfunction "VDD_62") (pintype "power_in"))
      (node (ref "U7") (pin "72") (pinfunction "VDD_72") (pintype "power_in"))
      (node (ref "U7") (pin "84") (pinfunction "VDD_84") (pintype "power_in"))
      (node (ref "U7") (pin "95") (pinfunction "VDD_95") (pintype "power_in"))
      (node (ref "U8") (pin "8") (pinfunction "VCC_8") (pintype "passive"))
      (node (ref "U9") (pin "1") (pinfunction "ENABLE_1") (pintype "input"))
      (node (ref "U9") (pin "8") (pinfunction "VCC_8") (pintype "power_in"))
      (node (ref "VR1") (pin "2") (pinfunction "Vout_2") (pintype "passive"))
      (node (ref "VR2") (pin "2") (pinfunction "Vout_2") (pintype "passive"))
    )
    (net (code "80") (name "5V") (class "Default")
      (node (ref "C16") (pin "2") (pinfunction "2_2") (pintype "passive"))
      (node (ref "C17") (pin "2") (pinfunction "2_2") (pintype "passive"))
      (node (ref "C21") (pin "2") (pinfunction "2_2") (pintype "passive"))
      (node (ref "C22") (pin "2") (pinfunction "2_2") (pintype "passive"))
      (node (ref "P1") (pin "1") (pinfunction "1_1") (pintype "passive"))
      (node (ref "P6") (pin "1") (pinfunction "1_1") (pintype "passive"))
      (node (ref "VR1") (pin "3") (pinfunction "Vin_3") (pintype "passive"))
      (node (ref "VR2") (pin "3") (pinfunction "Vin_3") (pintype "passive"))
    )
    (net (code "81") (name "GND") (class "Default")
      (node (ref "C16") (pin "1") (pinfunction "1_1") (pintype "passive"))
      (node (ref "C17") (pin "1") (pinfunction "1_1") (pintype "passive"))
      (node (ref "C18") (pin "1") (pinfunction "1_1") (pintype "passive"))
      (node (ref "C19") (pin "1") (pinfunction "1_1") (pintype "passive"))
      (node (ref "C20") (pin "2") (pinfunction "2_2") (pintype "passive"))
      (node (ref "C21") (pin "1") (pinfunction "1_1") (pintype "passive"))
      (node (ref "C22") (pin "1") (pinfunction "1_1") (pintype "passive"))
      (node (ref "C23") (pin "1") (pinfunction "1_1") (pintype "passive"))
      (node (ref "C24") (pin "1") (pinfunction "1_1") (pintype "passive"))
      (node (ref "C25") (pin "2") (pinfunction "2_2") (pintype "passive"))
      (node (ref "C26") (pin "1") (pinfunction "1_1") (pintype "passive"))
      (node (ref "C27") (pin "2") (pinfunction "2_2") (pintype "passive"))
      (node (ref "C28") (pin "1") (pinfunction "1_1") (pintype "passive"))
      (node (ref "C29") (pin "1") (pinfunction "1_1") (pintype "passive"))
      (node (ref "C30") (pin "2") (pinfunction "2_2") (pintype "passive"))
      (node (ref "C31") (pin "1") (pinfunction "1_1") (pintype "passive"))
      (node (ref "C32") (pin "2") (pinfunction "2_2") (pintype "passive"))
      (node (ref "C33") (pin "1") (pinfunction "1_1") (pintype "passive"))
      (node (ref "C34") (pin "2") (pinfunction "2_2") (pintype "passive"))
      (node (ref "C35") (pin "2") (pinfunction "2_2") (pintype "passive"))
      (node (ref "C36") (pin "1") (pinfunction "1_1") (pintype "passive"))
      (node (ref "C37") (pin "1") (pinfunction "1_1") (pintype "passive"))
      (node (ref "C38") (pin "1") (pinfunction "1_1") (pintype "passive"))
      (node (ref "C39") (pin "1") (pinfunction "1_1") (pintype "passive"))
      (node (ref "C40") (pin "1") (pinfunction "1_1") (pintype "passive"))
      (node (ref "C41") (pin "1") (pinfunction "1_1") (pintype "passive"))
      (node (ref "C42") (pin "1") (pinfunction "1_1") (pintype "passive"))
      (node (ref "C43") (pin "1") (pinfunction "1_1") (pintype "passive"))
      (node (ref "C44") (pin "1") (pinfunction "1_1") (pintype "passive"))
      (node (ref "C45") (pin "1") (pinfunction "1_1") (pintype "passive"))
      (node (ref "C46") (pin "1") (pinfunction "1_1") (pintype "passive"))
      (node (ref "C47") (pin "1") (pinfunction "1_1") (pintype "passive"))
      (node (ref "K1") (pin "3") (pinfunction "3_3") (pintype "passive"))
      (node (ref "K1") (pin "4") (pinfunction "4_4") (pintype "passive"))
      (node (ref "P1") (pin "2") (pinfunction "2_2") (pintype "passive"))
      (node (ref "P22") (pin "1") (pinfunction "1_1") (pintype "passive"))
      (node (ref "P6") (pin "2") (pinfunction "2_2") (pintype "passive"))
      (node (ref "P8") (pin "1") (pinfunction "1_1") (pintype "passive"))
      (node (ref "P9") (pin "1") (pinfunction "1_1") (pintype "passive"))
      (node (ref "Q1") (pin "2") (pinfunction "S_2") (pintype "passive"))
      (node (ref "Q2") (pin "2") (pinfunction "S_2") (pintype "passive"))
      (node (ref "R21") (pin "1") (pinfunction "1_1") (pintype "passive"))
      (node (ref "R26") (pin "1") (pinfunction "1_1") (pintype "passive"))
      (node (ref "R28") (pin "1") (pinfunction "1_1") (pintype "passive"))
      (node (ref "R29") (pin "1") (pinfunction "1_1") (pintype "passive"))
      (node (ref "R3") (pin "2") (pinfunction "2_2") (pintype "passive"))
      (node (ref "R32") (pin "1") (pinfunction "1_1") (pintype "passive"))
      (node (ref "TP1") (pin "0") (pinfunction "0_0") (pintype "passive"))
      (node (ref "U10") (pin "4") (pinfunction "GND_4") (pintype "power_in"))
      (node (ref "U7") (pin "107") (pinfunction "VSS_107") (pintype "power_in"))
      (node (ref "U7") (pin "120") (pinfunction "VSS_120") (pintype "power_in"))
      (node (ref "U7") (pin "130") (pinfunction "VSS_130") (pintype "power_in"))
      (node (ref "U7") (pin "16") (pinfunction "VSS_16") (pintype "power_in"))
      (node (ref "U7") (pin "31") (pinfunction "VSSA_31") (pintype "power_in"))
      (node (ref "U7") (pin "38") (pinfunction "VSS_38") (pintype "power_in"))
      (node (ref "U7") (pin "51") (pinfunction "VSS_51") (pintype "power_in"))
      (node (ref "U7") (pin "61") (pinfunction "VSS_61") (pintype "power_in"))
      (node (ref "U7") (pin "83") (pinfunction "VSS_83") (pintype "power_in"))
      (node (ref "U7") (pin "94") (pinfunction "VSS_94") (pintype "power_in"))
      (node (ref "U8") (pin "1") (pinfunction "A0_1") (pintype "passive"))
      (node (ref "U8") (pin "2") (pinfunction "A1_2") (pintype "passive"))
      (node (ref "U8") (pin "3") (pinfunction "A2_3") (pintype "passive"))
      (node (ref "U8") (pin "4") (pinfunction "VSS_4") (pintype "passive"))
      (node (ref "U9") (pin "4") (pinfunction "GND_4") (pintype "power_in"))
      (node (ref "VR1") (pin "1") (pinfunction "GND_1") (pintype "passive"))
      (node (ref "VR2") (pin "1") (pinfunction "GND_1") (pintype "passive"))
    )
    (net (code "82") (name "Net-(D1-PadK)") (class "Default")
      (node (ref "D1") (pin "K") (pinfunction "K_K") (pintype "passive"))
      (node (ref "R21") (pin "2") (pinfunction "2_2") (pintype "passive"))
    )
    (net (code "83") (name "Net-(LS1-B)") (class "Default")
      (node (ref "LS1") (pin "2") (pinfunction "B_2") (pintype "passive"))
      (node (ref "R22") (pin "2") (pinfunction "2_2") (pintype "passive"))
    )
    (net (code "84") (name "Net-(P9-Pad4)") (class "Default")
      (node (ref "P9") (pin "4") (pinfunction "4_4") (pintype "passive"))
      (node (ref "R43") (pin "1") (pinfunction "1_1") (pintype "passive"))
    )
    (net (code "85") (name "Net-(Q1-D)") (class "Default")
      (node (ref "Q1") (pin "3") (pinfunction "D_3") (pintype "passive"))
      (node (ref "R22") (pin "1") (pinfunction "1_1") (pintype "passive"))
    )
    (net (code "86") (name "Net-(Q1-G)") (class "Default")
      (node (ref "Q1") (pin "1") (pinfunction "G_1") (pintype "passive"))
      (node (ref "R25") (pin "1") (pinfunction "1_1") (pintype "passive"))
    )
    (net (code "87") (name "Net-(Q2-D)") (class "Default")
      (node (ref "Q2") (pin "3") (pinfunction "D_3") (pintype "passive"))
      (node (ref "R30") (pin "1") (pinfunction "1_1") (pintype "passive"))
      (node (ref "TP3") (pin "0") (pinfunction "0_0") (pintype "passive"))
      (node (ref "U8") (pin "7") (pinfunction "WP_7") (pintype "passive"))
    )
    (net (code "88") (name "Net-(Q2-G)") (class "Default")
      (node (ref "Q2") (pin "1") (pinfunction "G_1") (pintype "passive"))
      (node (ref "R31") (pin "1") (pinfunction "1_1") (pintype "passive"))
    )
    (net (code "89") (name "Net-(U7B-PDR_ON)") (class "Default")
      (node (ref "R27") (pin "1") (pinfunction "1_1") (pintype "passive"))
      (node (ref "R29") (pin "2") (pinfunction "2_2") (pintype "passive"))
      (node (ref "U7") (pin "143") (pinfunction "PDR_ON_143") (pintype "input"))
    )
    (net (code "90") (name "Net-(U7B-PH0{slash}OSC_IN)") (class "Default")
      (node (ref "C20") (pin "1") (pinfunction "1_1") (pintype "passive"))
      (node (ref "R23") (pin "2") (pinfunction "2_2") (pintype "passive"))
      (node (ref "U7") (pin "23") (pinfunction "PH0/OSC_IN_23") (pintype "bidirectional"))
      (node (ref "Y2") (pin "1") (pinfunction "OSC1_1") (pintype "passive"))
    )
    (net (code "91") (name "Net-(U7B-PH1{slash}OSC_OUT)") (class "Default")
      (node (ref "C25") (pin "1") (pinfunction "1_1") (pintype "passive"))
      (node (ref "R23") (pin "1") (pinfunction "1_1") (pintype "passive"))
      (node (ref "U7") (pin "24") (pinfunction "PH1/OSC_OUT_24") (pintype "bidirectional"))
      (node (ref "Y2") (pin "2") (pinfunction "OSC2_2") (pintype "passive"))
    )
    (net (code "92") (name "Net-(U7C-VCAP_1)") (class "Default")
      (node (ref "C32") (pin "1") (pinfunction "1_1") (pintype "passive"))
      (node (ref "U7") (pin "71") (pinfunction "VCAP_1_71") (pintype "power_in"))
    )
    (net (code "93") (name "Net-(U7C-VCAP_2)") (class "Default")
      (node (ref "C35") (pin "1") (pinfunction "1_1") (pintype "passive"))
      (node (ref "U7") (pin "106") (pinfunction "VCAP_2_106") (pintype "power_in"))
    )
    (net (code "94") (name "Net-(U9-READY)") (class "Default")
      (node (ref "R35") (pin "1") (pinfunction "1_1") (pintype "passive"))
      (node (ref "U9") (pin "5") (pinfunction "READY_5") (pintype "output"))
    )
    (net (code "95") (name "Net-(U10-READY)") (class "Default")
      (node (ref "R40") (pin "1") (pinfunction "1_1") (pintype "passive"))
      (node (ref "U10") (pin "5") (pinfunction "READY_5") (pintype "output"))
    )
    (net (code "96") (name "unconnected-(U7A-PA0{slash}WKUP-Pad34)") (class "Default")
      (node (ref "U7") (pin "34") (pinfunction "PA0/WKUP_34") (pintype "bidirectional"))
    )
    (net (code "97") (name "unconnected-(U7A-PA3-Pad37)") (class "Default")
      (node (ref "U7") (pin "37") (pinfunction "PA3_37") (pintype "bidirectional"))
    )
    (net (code "98") (name "unconnected-(U7A-PA4-Pad40)") (class "Default")
      (node (ref "U7") (pin "40") (pinfunction "PA4_40") (pintype "bidirectional"))
    )
    (net (code "99") (name "unconnected-(U7A-PA5-Pad41)") (class "Default")
      (node (ref "U7") (pin "41") (pinfunction "PA5_41") (pintype "bidirectional"))
    )
    (net (code "100") (name "unconnected-(U7A-PA6-Pad42)") (class "Default")
      (node (ref "U7") (pin "42") (pinfunction "PA6_42") (pintype "bidirectional"))
    )
    (net (code "101") (name "unconnected-(U7A-PA8-Pad100)") (class "Default")
      (node (ref "U7") (pin "100") (pinfunction "PA8_100") (pintype "bidirectional"))
    )
    (net (code "102") (name "unconnected-(U7A-PA15-Pad110)") (class "Default")
      (node (ref "U7") (pin "110") (pinfunction "PA15_110") (pintype "bidirectional"))
    )
    (net (code "103") (name "unconnected-(U7A-PB0-Pad46)") (class "Default")
      (node (ref "U7") (pin "46") (pinfunction "PB0_46") (pintype "bidirectional"))
    )
    (net (code "104") (name "unconnected-(U7A-PB1-Pad47)") (class "Default")
      (node (ref "U7") (pin "47") (pinfunction "PB1_47") (pintype "bidirectional"))
    )
    (net (code "105") (name "unconnected-(U7A-PB3-Pad133)") (class "Default")
      (node (ref "U7") (pin "133") (pinfunction "PB3_133") (pintype "bidirectional"))
    )
    (net (code "106") (name "unconnected-(U7A-PB4-Pad134)") (class "Default")
      (node (ref "U7") (pin "134") (pinfunction "PB4_134") (pintype "bidirectional"))
    )
    (net (code "107") (name "unconnected-(U7A-PB7-Pad137)") (class "Default")
      (node (ref "U7") (pin "137") (pinfunction "PB7_137") (pintype "bidirectional"))
    )
    (net (code "108") (name "unconnected-(U7A-PC0-Pad26)") (class "Default")
      (node (ref "U7") (pin "26") (pinfunction "PC0_26") (pintype "bidirectional"))
    )
    (net (code "109") (name "unconnected-(U7A-PC3-Pad29)") (class "Default")
      (node (ref "U7") (pin "29") (pinfunction "PC3_29") (pintype "bidirectional"))
    )
    (net (code "110") (name "unconnected-(U7A-PC12-Pad113)") (class "Default")
      (node (ref "U7") (pin "113") (pinfunction "PC12_113") (pintype "bidirectional"))
    )
    (net (code "111") (name "unconnected-(U7A-PC13-Pad7)") (class "Default")
      (node (ref "U7") (pin "7") (pinfunction "PC13_7") (pintype "bidirectional"))
    )
    (net (code "112") (name "unconnected-(U7A-PC14{slash}OSC32_IN-Pad8)") (class "Default")
      (node (ref "U7") (pin "8") (pinfunction "PC14/OSC32_IN_8") (pintype "bidirectional"))
    )
    (net (code "113") (name "unconnected-(U7A-PC15{slash}OSC32_OUT-Pad9)") (class "Default")
      (node (ref "U7") (pin "9") (pinfunction "PC15/OSC32_OUT_9") (pintype "bidirectional"))
    )
    (net (code "114") (name "unconnected-(U7A-PD0-Pad114)") (class "Default")
      (node (ref "U7") (pin "114") (pinfunction "PD0_114") (pintype "bidirectional"))
    )
    (net (code "115") (name "unconnected-(U7A-PD1-Pad115)") (class "Default")
      (node (ref "U7") (pin "115") (pinfunction "PD1_115") (pintype "bidirectional"))
    )
    (net (code "116") (name "unconnected-(U7A-PD2-Pad116)") (class "Default")
      (node (ref "U7") (pin "116") (pinfunction "PD2_116") (pintype "bidirectional"))
    )
    (net (code "117") (name "unconnected-(U7A-PD3-Pad117)") (class "Default")
      (node (ref "U7") (pin "117") (pinfunction "PD3_117") (pintype "bidirectional"))
    )
    (net (code "118") (name "unconnected-(U7A-PD4-Pad118)") (class "Default")
      (node (ref "U7") (pin "118") (pinfunction "PD4_118") (pintype "bidirectional"))
    )
    (net (code "119") (name "unconnected-(U7A-PD5-Pad119)") (class "Default")
      (node (ref "U7") (pin "119") (pinfunction "PD5_119") (pintype "bidirectional"))
    )
    (net (code "120") (name "unconnected-(U7A-PD6-Pad122)") (class "Default")
      (node (ref "U7") (pin "122") (pinfunction "PD6_122") (pintype "bidirectional"))
    )
    (net (code "121") (name "unconnected-(U7A-PD7-Pad123)") (class "Default")
      (node (ref "U7") (pin "123") (pinfunction "PD7_123") (pintype "bidirectional"))
    )
    (net (code "122") (name "unconnected-(U7A-PD8-Pad77)") (class "Default")
      (node (ref "U7") (pin "77") (pinfunction "PD8_77") (pintype "bidirectional"))
    )
    (net (code "123") (name "unconnected-(U7A-PD9-Pad78)") (class "Default")
      (node (ref "U7") (pin "78") (pinfunction "PD9_78") (pintype "bidirectional"))
    )
    (net (code "124") (name "unconnected-(U7A-PD10-Pad79)") (class "Default")
      (node (ref "U7") (pin "79") (pinfunction "PD10_79") (pintype "bidirectional"))
    )
    (net (code "125") (name "unconnected-(U7A-PD11-Pad80)") (class "Default")
      (node (ref "U7") (pin "80") (pinfunction "PD11_80") (pintype "bidirectional"))
    )
    (net (code "126") (name "unconnected-(U7A-PD12-Pad81)") (class "Default")
      (node (ref "U7") (pin "81") (pinfunction "PD12_81") (pintype "bidirectional"))
    )
    (net (code "127") (name "unconnected-(U7A-PD13-Pad82)") (class "Default")
      (node (ref "U7") (pin "82") (pinfunction "PD13_82") (pintype "bidirectional"))
    )
    (net (code "128") (name "unconnected-(U7A-PD14-Pad85)") (class "Default")
      (node (ref "U7") (pin "85") (pinfunction "PD14_85") (pintype "bidirectional"))
    )
    (net (code "129") (name "unconnected-(U7A-PD15-Pad86)") (class "Default")
      (node (ref "U7") (pin "86") (pinfunction "PD15_86") (pintype "bidirectional"))
    )
    (net (code "130") (name "unconnected-(U7B-PE2-Pad1)") (class "Default")
      (node (ref "U7") (pin "1") (pinfunction "PE2_1") (pintype "bidirectional"))
    )
    (net (code "131") (name "unconnected-(U7B-PE3-Pad2)") (class "Default")
      (node (ref "U7") (pin "2") (pinfunction "PE3_2") (pintype "bidirectional"))
    )
    (net (code "132") (name "unconnected-(U7B-PE4-Pad3)") (class "Default")
      (node (ref "U7") (pin "3") (pinfunction "PE4_3") (pintype "bidirectional"))
    )
    (net (code "133") (name "unconnected-(U7B-PE5-Pad4)") (class "Default")
      (node (ref "U7") (pin "4") (pinfunction "PE5_4") (pintype "bidirectional"))
    )
    (net (code "134") (name "unconnected-(U7B-PE6-Pad5)") (class "Default")
      (node (ref "U7") (pin "5") (pinfunction "PE6_5") (pintype "bidirectional"))
    )
    (net (code "135") (name "unconnected-(U7B-PF7-Pad19)") (class "Default")
      (node (ref "U7") (pin "19") (pinfunction "PF7_19") (pintype "bidirectional"))
    )
    (net (code "136") (name "unconnected-(U7B-PF8-Pad20)") (class "Default")
      (node (ref "U7") (pin "20") (pinfunction "PF8_20") (pintype "bidirectional"))
    )
    (net (code "137") (name "unconnected-(U7B-PF10-Pad22)") (class "Default")
      (node (ref "U7") (pin "22") (pinfunction "PF10_22") (pintype "bidirectional"))
    )
  )
)
